# audio.net
KiCad netlist of a schematic drawn in Altium Designer
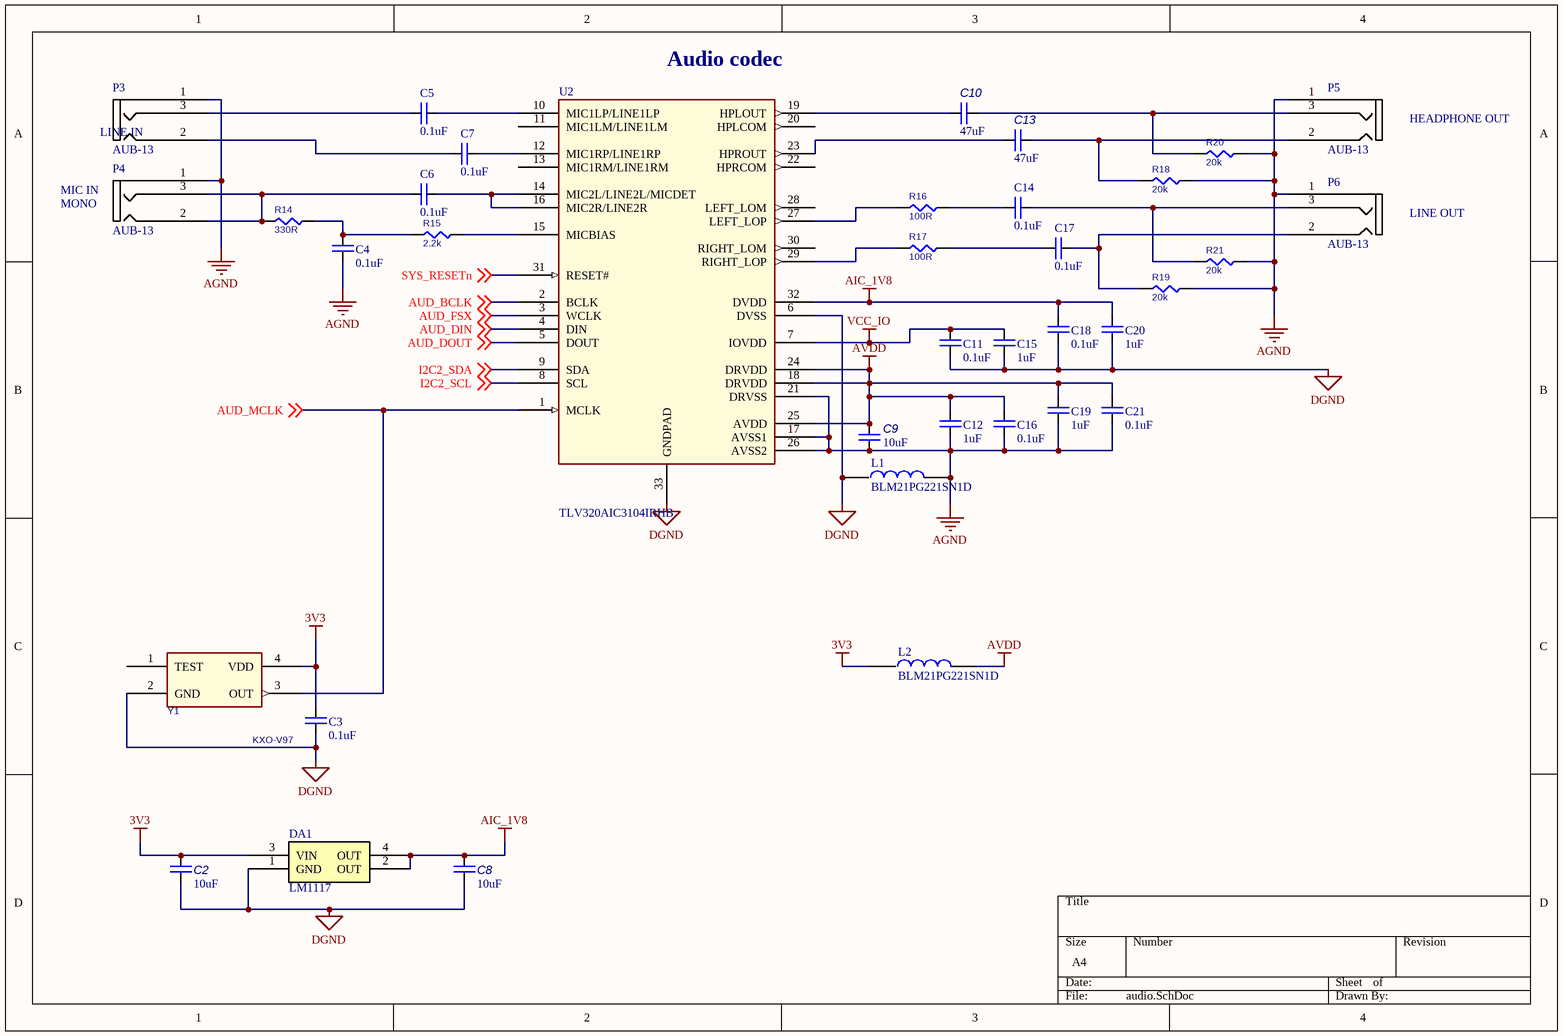
[diagram p0: audio.SchDoc]

(export (version "E")
  (design (tool "Eeschema 10.0.6"))
  (components
    (comp (ref "C2")
      (value "10uF")
      (footprint "CC2012-0805")
      (description "C0805")
      (libsource (lib "usomiq-audio") (part "C0805"))
    )
    (comp (ref "C3")
      (value "0.1uF")
      (footprint "CHIP0603")
      (description "Ceramic capacitor C0603")
      (fields (field (name "Comment") "C0603"))
      (libsource (lib "usomiq-audio") (part "C0603"))
    )
    (comp (ref "C4")
      (value "0.1uF")
      (footprint "CHIP0603")
      (description "Ceramic capacitor C0603")
      (fields (field (name "Comment") "C0603"))
      (libsource (lib "usomiq-audio") (part "C0603"))
    )
    (comp (ref "C5")
      (value "0.1uF")
      (footprint "CHIP0603")
      (description "Ceramic capacitor C0603")
      (fields (field (name "Comment") "C0603"))
      (libsource (lib "usomiq-audio") (part "C0603"))
    )
    (comp (ref "C6")
      (value "0.1uF")
      (footprint "CHIP0603")
      (description "Ceramic capacitor C0603")
      (fields (field (name "Comment") "C0603"))
      (libsource (lib "usomiq-audio") (part "C0603"))
    )
    (comp (ref "C7")
      (value "0.1uF")
      (footprint "CHIP0603")
      (description "Ceramic capacitor C0603")
      (fields (field (name "Comment") "C0603"))
      (libsource (lib "usomiq-audio") (part "C0603"))
    )
    (comp (ref "C8")
      (value "10uF")
      (footprint "CC2012-0805")
      (description "C0805")
      (libsource (lib "usomiq-audio") (part "C0805"))
    )
    (comp (ref "C9")
      (value "10uF")
      (footprint "CC2012-0805")
      (description "C0805")
      (libsource (lib "usomiq-audio") (part "C0805"))
    )
    (comp (ref "C10")
      (value "47uF")
      (footprint "CC3216-1206")
      (description "C1206")
      (libsource (lib "usomiq-audio") (part "C1206"))
    )
    (comp (ref "C11")
      (value "0.1uF")
      (footprint "CHIP0603")
      (description "Ceramic capacitor C0603")
      (fields (field (name "Comment") "C0603"))
      (libsource (lib "usomiq-audio") (part "C0603"))
    )
    (comp (ref "C12")
      (value "1uF")
      (footprint "CHIP0603")
      (description "Ceramic capacitor C0603")
      (fields (field (name "Comment") "C0603"))
      (libsource (lib "usomiq-audio") (part "C0603"))
    )
    (comp (ref "C13")
      (value "47uF")
      (footprint "CC3216-1206")
      (description "C1206")
      (libsource (lib "usomiq-audio") (part "C1206"))
    )
    (comp (ref "C14")
      (value "0.1uF")
      (footprint "CHIP0603")
      (description "Ceramic capacitor C0603")
      (fields (field (name "Comment") "C0603"))
      (libsource (lib "usomiq-audio") (part "C0603"))
    )
    (comp (ref "C15")
      (value "1uF")
      (footprint "CHIP0603")
      (description "Ceramic capacitor C0603")
      (fields (field (name "Comment") "C0603"))
      (libsource (lib "usomiq-audio") (part "C0603"))
    )
    (comp (ref "C16")
      (value "0.1uF")
      (footprint "CHIP0603")
      (description "Ceramic capacitor C0603")
      (fields (field (name "Comment") "C0603"))
      (libsource (lib "usomiq-audio") (part "C0603"))
    )
    (comp (ref "C17")
      (value "0.1uF")
      (footprint "CHIP0603")
      (description "Ceramic capacitor C0603")
      (fields (field (name "Comment") "C0603"))
      (libsource (lib "usomiq-audio") (part "C0603"))
    )
    (comp (ref "C18")
      (value "0.1uF")
      (footprint "CHIP0603")
      (description "Ceramic capacitor C0603")
      (fields (field (name "Comment") "C0603"))
      (libsource (lib "usomiq-audio") (part "C0603"))
    )
    (comp (ref "C19")
      (value "1uF")
      (footprint "CHIP0603")
      (description "Ceramic capacitor C0603")
      (fields (field (name "Comment") "C0603"))
      (libsource (lib "usomiq-audio") (part "C0603"))
    )
    (comp (ref "C20")
      (value "1uF")
      (footprint "CHIP0603")
      (description "Ceramic capacitor C0603")
      (fields (field (name "Comment") "C0603"))
      (libsource (lib "usomiq-audio") (part "C0603"))
    )
    (comp (ref "C21")
      (value "0.1uF")
      (footprint "CHIP0603")
      (description "Ceramic capacitor C0603")
      (fields (field (name "Comment") "C0603"))
      (libsource (lib "usomiq-audio") (part "C0603"))
    )
    (comp (ref "DA1")
      (value "LM1117")
      (footprint "SOT230P700X160-4N")
      (description "800mA Low-Dropout Linear Regulator")
      (fields (field (name "MANUFACTURER") "National"))
      (libsource (lib "usomiq-audio") (part "LM1117"))
    )
    (comp (ref "L1")
      (value "BLM21PG221SN1D")
      (footprint "Chip2PinSM127P600-8N")
      (fields (field (name "MANUFACTURER") "Murata"))
      (libsource (lib "usomiq-audio") (part "BLM21PG221SN1D"))
    )
    (comp (ref "L2")
      (value "BLM21PG221SN1D")
      (footprint "Chip2PinSM127P600-8N")
      (fields (field (name "MANUFACTURER") "Murata"))
      (libsource (lib "usomiq-audio") (part "BLM21PG221SN1D"))
    )
    (comp (ref "P3")
      (value "AUB-13")
      (footprint "AUB_13")
      (description "Audio connector mini-jack 3.5mm, 3 pins")
      (libsource (lib "usomiq-audio") (part "AUB-13"))
    )
    (comp (ref "P4")
      (value "AUB-13")
      (footprint "AUB_13")
      (description "Audio connector mini-jack 3.5mm, 3 pins")
      (libsource (lib "usomiq-audio") (part "AUB-13"))
    )
    (comp (ref "P5")
      (value "AUB-13")
      (footprint "AUB_13")
      (description "Audio connector mini-jack 3.5mm, 3 pins")
      (libsource (lib "usomiq-audio") (part "AUB-13"))
    )
    (comp (ref "P6")
      (value "AUB-13")
      (footprint "AUB_13")
      (description "Audio connector mini-jack 3.5mm, 3 pins")
      (libsource (lib "usomiq-audio") (part "AUB-13"))
    )
    (comp (ref "R14")
      (value "330R")
      (footprint "CHIP0603")
      (description "Resistor 0603")
      (fields (field (name "Comment") "R0603"))
      (libsource (lib "usomiq-audio") (part "R0603"))
    )
    (comp (ref "R15")
      (value "2.2k")
      (footprint "CHIP0603")
      (description "Resistor 0603")
      (fields (field (name "Comment") "R0603"))
      (libsource (lib "usomiq-audio") (part "R0603"))
    )
    (comp (ref "R16")
      (value "100R")
      (footprint "CHIP0603")
      (description "Resistor 0603")
      (fields (field (name "Comment") "R0603"))
      (libsource (lib "usomiq-audio") (part "R0603"))
    )
    (comp (ref "R17")
      (value "100R")
      (footprint "CHIP0603")
      (description "Resistor 0603")
      (fields (field (name "Comment") "R0603"))
      (libsource (lib "usomiq-audio") (part "R0603"))
    )
    (comp (ref "R18")
      (value "20k")
      (footprint "CHIP0603")
      (description "Resistor 0603")
      (fields (field (name "Comment") "R0603"))
      (libsource (lib "usomiq-audio") (part "R0603"))
    )
    (comp (ref "R19")
      (value "20k")
      (footprint "CHIP0603")
      (description "Resistor 0603")
      (fields (field (name "Comment") "R0603"))
      (libsource (lib "usomiq-audio") (part "R0603"))
    )
    (comp (ref "R20")
      (value "20k")
      (footprint "CHIP0603")
      (description "Resistor 0603")
      (fields (field (name "Comment") "R0603"))
      (libsource (lib "usomiq-audio") (part "R0603"))
    )
    (comp (ref "R21")
      (value "20k")
      (footprint "CHIP0603")
      (description "Resistor 0603")
      (fields (field (name "Comment") "R0603"))
      (libsource (lib "usomiq-audio") (part "R0603"))
    )
    (comp (ref "U2")
      (value "TLV320AIC3104")
      (footprint "QFN32")
      (description "LOW-POWER STEREO AUDIO CODEC FOR PORTABLE AUDIO/TELEPHONY")
      (fields (field (name "MANUFACTURER") "TI") (field (name "MAN P/N") "TLV320AIC3104IRHB"))
      (libsource (lib "usomiq-audio") (part "TLV320AIC3104"))
    )
    (comp (ref "Y1")
      (value "KXO-V97")
      (footprint "KXO_V97")
      (description "Quartz oscillator 7x5mm")
      (fields (field (name "MANUFACTURER") "Geyer"))
      (libsource (lib "usomiq-audio") (part "KXO-V97"))
    )
  )
  (nets
    (net (code "1") (name "3V3") (class "Default")
      (node (ref "C2") (pin "2") (pinfunction "2_2") (pintype "passive"))
      (node (ref "C3") (pin "1") (pinfunction "1_1") (pintype "passive"))
      (node (ref "DA1") (pin "3") (pinfunction "VIN_3") (pintype "power_in"))
      (node (ref "L2") (pin "1") (pinfunction "1_1") (pintype "passive"))
      (node (ref "Y1") (pin "4") (pinfunction "VDD_4") (pintype "power_in"))
    )
    (net (code "2") (name "AGND") (class "Default")
      (node (ref "C12") (pin "2") (pinfunction "2_2") (pintype "passive"))
      (node (ref "C16") (pin "2") (pinfunction "2_2") (pintype "passive"))
      (node (ref "C19") (pin "2") (pinfunction "2_2") (pintype "passive"))
      (node (ref "C21") (pin "2") (pinfunction "2_2") (pintype "passive"))
      (node (ref "C4") (pin "1") (pinfunction "1_1") (pintype "passive"))
      (node (ref "C9") (pin "1") (pinfunction "1_1") (pintype "passive"))
      (node (ref "L1") (pin "2") (pinfunction "2_2") (pintype "passive"))
      (node (ref "P3") (pin "1") (pinfunction "GND_1") (pintype "passive"))
      (node (ref "P4") (pin "1") (pinfunction "GND_1") (pintype "passive"))
      (node (ref "P5") (pin "1") (pinfunction "GND_1") (pintype "passive"))
      (node (ref "P6") (pin "1") (pinfunction "GND_1") (pintype "passive"))
      (node (ref "R18") (pin "1") (pinfunction "1_1") (pintype "passive"))
      (node (ref "R19") (pin "1") (pinfunction "1_1") (pintype "passive"))
      (node (ref "R20") (pin "1") (pinfunction "1_1") (pintype "passive"))
      (node (ref "R21") (pin "1") (pinfunction "1_1") (pintype "passive"))
      (node (ref "U2") (pin "17") (pinfunction "AVSS1_17") (pintype "power_in"))
      (node (ref "U2") (pin "21") (pinfunction "DRVSS_21") (pintype "power_in"))
      (node (ref "U2") (pin "26") (pinfunction "AVSS2_26") (pintype "power_in"))
    )
    (net (code "3") (name "AIC_1V8") (class "Default")
      (node (ref "C18") (pin "1") (pinfunction "1_1") (pintype "passive"))
      (node (ref "C20") (pin "1") (pinfunction "1_1") (pintype "passive"))
      (node (ref "C8") (pin "2") (pinfunction "2_2") (pintype "passive"))
      (node (ref "DA1") (pin "2") (pinfunction "OUT_2") (pintype "power_in"))
      (node (ref "DA1") (pin "4") (pinfunction "OUT_4") (pintype "power_in"))
      (node (ref "U2") (pin "32") (pinfunction "DVDD_32") (pintype "power_in"))
    )
    (net (code "4") (name "AUD_BCLK") (class "Default")
      (node (ref "U2") (pin "2") (pinfunction "BCLK_2") (pintype "passive"))
    )
    (net (code "5") (name "AUD_DIN") (class "Default")
      (node (ref "U2") (pin "4") (pinfunction "DIN_4") (pintype "passive"))
    )
    (net (code "6") (name "AUD_DOUT") (class "Default")
      (node (ref "U2") (pin "5") (pinfunction "DOUT_5") (pintype "passive"))
    )
    (net (code "7") (name "AUD_FSX") (class "Default")
      (node (ref "U2") (pin "3") (pinfunction "WCLK_3") (pintype "passive"))
    )
    (net (code "8") (name "AUD_MCLK") (class "Default")
      (node (ref "U2") (pin "1") (pinfunction "MCLK_1") (pintype "input"))
      (node (ref "Y1") (pin "3") (pinfunction "OUT_3") (pintype "output"))
    )
    (net (code "9") (name "AVDD") (class "Default")
      (node (ref "C12") (pin "1") (pinfunction "1_1") (pintype "passive"))
      (node (ref "C16") (pin "1") (pinfunction "1_1") (pintype "passive"))
      (node (ref "C19") (pin "1") (pinfunction "1_1") (pintype "passive"))
      (node (ref "C21") (pin "1") (pinfunction "1_1") (pintype "passive"))
      (node (ref "C9") (pin "2") (pinfunction "2_2") (pintype "passive"))
      (node (ref "L2") (pin "2") (pinfunction "2_2") (pintype "passive"))
      (node (ref "U2") (pin "18") (pinfunction "DRVDD_18") (pintype "power_in"))
      (node (ref "U2") (pin "24") (pinfunction "DRVDD_24") (pintype "power_in"))
      (node (ref "U2") (pin "25") (pinfunction "AVDD_25") (pintype "power_in"))
    )
    (net (code "10") (name "DGND") (class "Default")
      (node (ref "C11") (pin "2") (pinfunction "2_2") (pintype "passive"))
      (node (ref "C15") (pin "2") (pinfunction "2_2") (pintype "passive"))
      (node (ref "C18") (pin "2") (pinfunction "2_2") (pintype "passive"))
      (node (ref "C2") (pin "1") (pinfunction "1_1") (pintype "passive"))
      (node (ref "C20") (pin "2") (pinfunction "2_2") (pintype "passive"))
      (node (ref "C3") (pin "2") (pinfunction "2_2") (pintype "passive"))
      (node (ref "C8") (pin "1") (pinfunction "1_1") (pintype "passive"))
      (node (ref "DA1") (pin "1") (pinfunction "GND_1") (pintype "power_in"))
      (node (ref "L1") (pin "1") (pinfunction "1_1") (pintype "passive"))
      (node (ref "U2") (pin "33") (pinfunction "GNDPAD_33") (pintype "power_in"))
      (node (ref "U2") (pin "6") (pinfunction "DVSS_6") (pintype "power_in"))
      (node (ref "Y1") (pin "2") (pinfunction "GND_2") (pintype "power_in"))
    )
    (net (code "11") (name "I2C2_SCL") (class "Default")
      (node (ref "U2") (pin "8") (pinfunction "SCL_8") (pintype "passive"))
    )
    (net (code "12") (name "I2C2_SDA") (class "Default")
      (node (ref "U2") (pin "9") (pinfunction "SDA_9") (pintype "passive"))
    )
    (net (code "13") (name "Net-(C4-Pad2)") (class "Default")
      (node (ref "C4") (pin "2") (pinfunction "2_2") (pintype "passive"))
      (node (ref "R14") (pin "2") (pinfunction "2_2") (pintype "passive"))
      (node (ref "R15") (pin "1") (pinfunction "1_1") (pintype "passive"))
    )
    (net (code "14") (name "Net-(C14-Pad1)") (class "Default")
      (node (ref "C14") (pin "1") (pinfunction "1_1") (pintype "passive"))
      (node (ref "R16") (pin "2") (pinfunction "2_2") (pintype "passive"))
    )
    (net (code "15") (name "Net-(C17-Pad1)") (class "Default")
      (node (ref "C17") (pin "1") (pinfunction "1_1") (pintype "passive"))
      (node (ref "R17") (pin "2") (pinfunction "2_2") (pintype "passive"))
    )
    (net (code "16") (name "Net-(P3-LEFT)") (class "Default")
      (node (ref "C5") (pin "1") (pinfunction "1_1") (pintype "passive"))
      (node (ref "P3") (pin "3") (pinfunction "LEFT_3") (pintype "passive"))
    )
    (net (code "17") (name "Net-(P3-RIGHT)") (class "Default")
      (node (ref "C7") (pin "1") (pinfunction "1_1") (pintype "passive"))
      (node (ref "P3") (pin "2") (pinfunction "RIGHT_2") (pintype "passive"))
    )
    (net (code "18") (name "Net-(P4-LEFT)") (class "Default")
      (node (ref "C6") (pin "1") (pinfunction "1_1") (pintype "passive"))
      (node (ref "P4") (pin "2") (pinfunction "RIGHT_2") (pintype "passive"))
      (node (ref "P4") (pin "3") (pinfunction "LEFT_3") (pintype "passive"))
      (node (ref "R14") (pin "1") (pinfunction "1_1") (pintype "passive"))
    )
    (net (code "19") (name "Net-(P5-LEFT)") (class "Default")
      (node (ref "C10") (pin "1") (pinfunction "1_1") (pintype "passive"))
      (node (ref "P5") (pin "3") (pinfunction "LEFT_3") (pintype "passive"))
      (node (ref "R20") (pin "2") (pinfunction "2_2") (pintype "passive"))
    )
    (net (code "20") (name "Net-(P5-RIGHT)") (class "Default")
      (node (ref "C13") (pin "1") (pinfunction "1_1") (pintype "passive"))
      (node (ref "P5") (pin "2") (pinfunction "RIGHT_2") (pintype "passive"))
      (node (ref "R18") (pin "2") (pinfunction "2_2") (pintype "passive"))
    )
    (net (code "21") (name "Net-(P6-LEFT)") (class "Default")
      (node (ref "C14") (pin "2") (pinfunction "2_2") (pintype "passive"))
      (node (ref "P6") (pin "3") (pinfunction "LEFT_3") (pintype "passive"))
      (node (ref "R21") (pin "2") (pinfunction "2_2") (pintype "passive"))
    )
    (net (code "22") (name "Net-(P6-RIGHT)") (class "Default")
      (node (ref "C17") (pin "2") (pinfunction "2_2") (pintype "passive"))
      (node (ref "P6") (pin "2") (pinfunction "RIGHT_2") (pintype "passive"))
      (node (ref "R19") (pin "2") (pinfunction "2_2") (pintype "passive"))
    )
    (net (code "23") (name "Net-(U2-HPLOUT)") (class "Default")
      (node (ref "C10") (pin "2") (pinfunction "2_2") (pintype "passive"))
      (node (ref "U2") (pin "19") (pinfunction "HPLOUT_19") (pintype "output"))
    )
    (net (code "24") (name "Net-(U2-HPROUT)") (class "Default")
      (node (ref "C13") (pin "2") (pinfunction "2_2") (pintype "passive"))
      (node (ref "U2") (pin "23") (pinfunction "HPROUT_23") (pintype "output"))
    )
    (net (code "25") (name "Net-(U2-LEFT_LOP)") (class "Default")
      (node (ref "R16") (pin "1") (pinfunction "1_1") (pintype "passive"))
      (node (ref "U2") (pin "27") (pinfunction "LEFT_LOP_27") (pintype "output"))
    )
    (net (code "26") (name "Net-(U2-MIC1LP{slash}LINE1LP)") (class "Default")
      (node (ref "C5") (pin "2") (pinfunction "2_2") (pintype "passive"))
      (node (ref "U2") (pin "10") (pinfunction "MIC1LP/LINE1LP_10") (pintype "passive"))
    )
    (net (code "27") (name "Net-(U2-MIC1RP{slash}LINE1RP)") (class "Default")
      (node (ref "C7") (pin "2") (pinfunction "2_2") (pintype "passive"))
      (node (ref "U2") (pin "12") (pinfunction "MIC1RP/LINE1RP_12") (pintype "passive"))
    )
    (net (code "28") (name "Net-(U2-MIC2L{slash}LINE2L{slash}MICDET)") (class "Default")
      (node (ref "C6") (pin "2") (pinfunction "2_2") (pintype "passive"))
      (node (ref "U2") (pin "14") (pinfunction "MIC2L/LINE2L/MICDET_14") (pintype "passive"))
      (node (ref "U2") (pin "16") (pinfunction "MIC2R/LINE2R_16") (pintype "passive"))
    )
    (net (code "29") (name "Net-(U2-MICBIAS)") (class "Default")
      (node (ref "R15") (pin "2") (pinfunction "2_2") (pintype "passive"))
      (node (ref "U2") (pin "15") (pinfunction "MICBIAS_15") (pintype "passive"))
    )
    (net (code "30") (name "Net-(U2-RIGHT_LOP)") (class "Default")
      (node (ref "R17") (pin "1") (pinfunction "1_1") (pintype "passive"))
      (node (ref "U2") (pin "29") (pinfunction "RIGHT_LOP_29") (pintype "output"))
    )
    (net (code "31") (name "SYS_RESETn") (class "Default")
      (node (ref "U2") (pin "31") (pinfunction "RESET#_31") (pintype "input"))
    )
    (net (code "32") (name "VCC_IO") (class "Default")
      (node (ref "C11") (pin "1") (pinfunction "1_1") (pintype "passive"))
      (node (ref "C15") (pin "1") (pinfunction "1_1") (pintype "passive"))
      (node (ref "U2") (pin "7") (pinfunction "IOVDD_7") (pintype "power_in"))
    )
    (net (code "33") (name "unconnected-(U2-HPLCOM-Pad20)") (class "Default")
      (node (ref "U2") (pin "20") (pinfunction "HPLCOM_20") (pintype "output"))
    )
    (net (code "34") (name "unconnected-(U2-HPRCOM-Pad22)") (class "Default")
      (node (ref "U2") (pin "22") (pinfunction "HPRCOM_22") (pintype "output"))
    )
    (net (code "35") (name "unconnected-(U2-LEFT_LOM-Pad28)") (class "Default")
      (node (ref "U2") (pin "28") (pinfunction "LEFT_LOM_28") (pintype "output"))
    )
    (net (code "36") (name "unconnected-(U2-MIC1LM{slash}LINE1LM-Pad11)") (class "Default")
      (node (ref "U2") (pin "11") (pinfunction "MIC1LM/LINE1LM_11") (pintype "passive"))
    )
    (net (code "37") (name "unconnected-(U2-MIC1RM{slash}LINE1RM-Pad13)") (class "Default")
      (node (ref "U2") (pin "13") (pinfunction "MIC1RM/LINE1RM_13") (pintype "passive"))
    )
    (net (code "38") (name "unconnected-(U2-RIGHT_LOM-Pad30)") (class "Default")
      (node (ref "U2") (pin "30") (pinfunction "RIGHT_LOM_30") (pintype "output"))
    )
    (net (code "39") (name "unconnected-(Y1-TEST-Pad1)") (class "Default")
      (node (ref "Y1") (pin "1") (pinfunction "TEST_1") (pintype "passive"))
    )
  )
)
